# LPEDT_revA1_bikeit_MCU_RADIO.net
KiCad netlist of a schematic drawn in Altium Designer
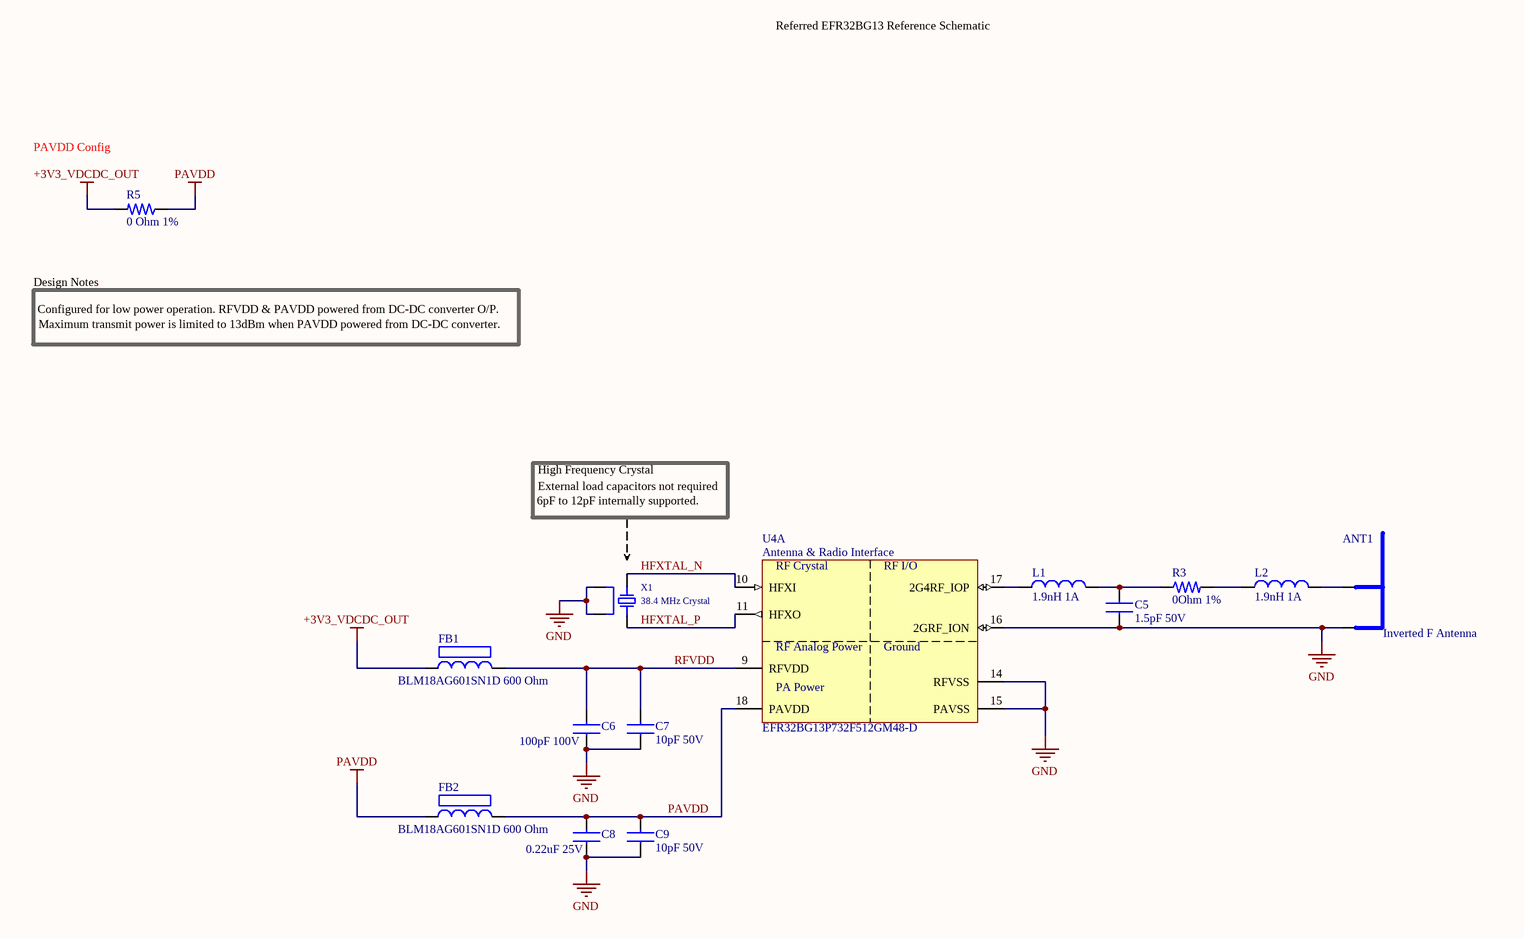
[diagram p0: LPEDT_revA1_bikeit_MCU_RADIO.SchDoc]

(export (version "E")
  (design (tool "Eeschema 10.0.6"))
  (components
    (comp (ref "ANT1")
      (value "Inverted F Antenna")
      (description "Inverted F antenna for BT")
      (libsource (lib "LPEDT_revA1_bikeit_IL") (part "Inverted F Antenna"))
    )
    (comp (ref "C5")
      (value "1.5pF 50V")
      (footprint "CAP_0403_1.00mm*0.50mm")
      (description "1.5pF ±0.1pF 50V Ceramic Capacitor C0G, NP0 0402 (1005 Metric)")
      (fields
        (field (name "MANUFACTURER") "Johanson Technology Inc.")
        (field (name "MANUFACTURER PART NUMBER") "500R07S1R5BV4T")
      )
      (libsource (lib "LPEDT_revA1_bikeit") (part "500R07S1R5BV4T"))
    )
    (comp (ref "C6")
      (value "100pF 100V")
      (footprint "CAP_0603_1.60mm*0.80mm")
      (description "Multilayer Ceramic Capacitors MLCC - SMD/SMT 100pF 100Volts C0G 0.01")
      (fields
        (field (name "MANUFACTURER") "Murata")
        (field (name "MANUFACTURER PART NUMBER") "GRM1885C2A101FA01D")
      )
      (libsource (lib "LPEDT_revA1_bikeit_IL") (part "GRM1885C2A101FA01D"))
    )
    (comp (ref "C7")
      (value "10pF 50V")
      (footprint "CAP_0603_1.60mm*0.80mm")
      (description "Cap Ceramic 10pF 50V C0G 1% SMD 0603 125C T/R")
      (fields
        (field (name "MANUFACTURER") "Murata")
        (field (name "MANUFACTURER PART NUMBER") "GRM1885C1H100FA01D")
      )
      (libsource (lib "LPEDT_revA1_bikeit_IL") (part "GRM1885C1H100FA01D"))
    )
    (comp (ref "C8")
      (value "0.22uF 25V")
      (footprint "CAP_0603_1.60mm*0.80mm")
      (description "Capacitor 220 nF 25 VDC PU=4000 ST, GRM188R71E224KA88D, Murata")
      (fields
        (field (name "MANUFACTURER") "Murata")
        (field (name "MANUFACTURER PART NUMBER") "GRM188R71E224KA88D")
      )
      (libsource (lib "LPEDT_revA1_bikeit_IL") (part "GRM188R71E224KA88D"))
    )
    (comp (ref "C9")
      (value "10pF 50V")
      (footprint "CAP_0603_1.60mm*0.80mm")
      (description "Cap Ceramic 10pF 50V C0G 1% SMD 0603 125C T/R")
      (fields
        (field (name "MANUFACTURER") "Murata")
        (field (name "MANUFACTURER PART NUMBER") "GRM1885C1H100FA01D")
      )
      (libsource (lib "LPEDT_revA1_bikeit_IL") (part "GRM1885C1H100FA01D"))
    )
    (comp (ref "FB1")
      (value "BLM18AG601SN1D 600 Ohm")
      (footprint "Chip2PinSM127P600-8N")
      (description "Ferrite Bead, 0603 / 1608, 600 ohm, 500 mA, Série BLM18A, 0.38 ohm, ± 25%")
      (fields
        (field (name "MANUFACTURER") "Murata")
        (field (name "MANUFACTURER PART NUMBER") "BLM18AG601SN1D")
      )
      (libsource (lib "LPEDT_revA1_bikeit_IL") (part "BLM18AG601SN1D"))
    )
    (comp (ref "FB2")
      (value "BLM18AG601SN1D 600 Ohm")
      (footprint "Chip2PinSM127P600-8N")
      (description "Ferrite Bead, 0603 / 1608, 600 ohm, 500 mA, Série BLM18A, 0.38 ohm, ± 25%")
      (fields
        (field (name "MANUFACTURER") "Murata")
        (field (name "MANUFACTURER PART NUMBER") "BLM18AG601SN1D")
      )
      (libsource (lib "LPEDT_revA1_bikeit_IL") (part "BLM18AG601SN1D"))
    )
    (comp (ref "L1")
      (value "1.9nH 1A")
      (description "1.9nH Unshielded Multilayer Inductor 1A 50mOhm Max 0402 (1005 Metric)")
      (libsource (lib "LPEDT_revA1_bikeit_IL") (part "LQG15WZ1N9S02D"))
    )
    (comp (ref "L2")
      (value "1.9nH 1A")
      (description "1.9nH Unshielded Multilayer Inductor 1A 50mOhm Max 0402 (1005 Metric)")
      (libsource (lib "LPEDT_revA1_bikeit_IL") (part "LQG15WZ1N9S02D"))
    )
    (comp (ref "R3")
      (value "0Ohm 1%")
      (footprint "RESC1005X04N")
      (description "RES 0 OHM JUMPER 1/16W 0402")
      (fields
        (field (name "MANUFACTURER") "Stackpole Electronics")
        (field (name "MANUFACTURER PART NUMBER") "RMCF0402ZT0R00")
      )
      (libsource (lib "LPEDT_revA1_bikeit_IL") (part "RMCF0402ZT0R00"))
    )
    (comp (ref "R5")
      (value "0 Ohm 1%")
      (footprint "RESC1005X04N")
      (description "RES 0 OHM JUMPER 1/16W 0402")
      (fields
        (field (name "MANUFACTURER") "Stackpole Electronics")
        (field (name "MANUFACTURER PART NUMBER") "RMCF0402ZT0R00")
      )
      (libsource (lib "LPEDT_revA1_bikeit_IL") (part "RMCF0402ZT0R00"))
    )
    (comp (ref "U4")
      (value "EFR32BG13P732F512GM48-D")
      (footprint "QFN50P700X700X90_HS-49N")
      (description "BLUE GECKO QFN48 2.4 GHZ 512KB 6")
      (fields (field (name "MANUFACTURER") "Silicon Labs"))
      (libsource (lib "LPEDT_revA1_bikeit") (part "EFR32BG13P732F512GM48-D"))
    )
    (comp (ref "X1")
      (value "38.4 MHz Crystal")
      (description "CRYSTAL 38.4000MHZ 8PF SMD")
      (fields
        (field (name "MANUFACTURER") "Kyocera AVX")
        (field (name "MANUFACTURER PART NUMBER") "CX2016DB38400D0FLJCC")
      )
      (libsource (lib "LPEDT_revA1_bikeit") (part "CX2016DB38400D0FLJCC"))
    )
  )
  (nets
    (net (code "1") (name "+3V3_VDCDC_OUT") (class "Default")
      (node (ref "FB1") (pin "1") (pinfunction "1_1") (pintype "passive"))
      (node (ref "R5") (pin "2") (pinfunction "2_2") (pintype "passive"))
    )
    (net (code "2") (name "/HFXTAL_N") (class "Default")
      (node (ref "U4") (pin "10") (pinfunction "HFXI_10") (pintype "input"))
      (node (ref "X1") (pin "3") (pinfunction "HOT_3") (pintype "passive"))
    )
    (net (code "3") (name "/HFXTAL_P") (class "Default")
      (node (ref "U4") (pin "11") (pinfunction "HFXO_11") (pintype "output"))
      (node (ref "X1") (pin "1") (pinfunction "HOT_1") (pintype "passive"))
    )
    (net (code "4") (name "/RFVDD") (class "Default")
      (node (ref "C6") (pin "1") (pinfunction "1_1") (pintype "passive"))
      (node (ref "C7") (pin "1") (pinfunction "1_1") (pintype "passive"))
      (node (ref "FB1") (pin "2") (pinfunction "2_2") (pintype "passive"))
      (node (ref "U4") (pin "9") (pinfunction "RFVDD_9") (pintype "power_in"))
    )
    (net (code "5") (name "GND") (class "Default")
      (node (ref "ANT1") (pin "2") (pinfunction "GND_2") (pintype "power_in"))
      (node (ref "C5") (pin "2") (pinfunction "2_2") (pintype "passive"))
      (node (ref "C6") (pin "2") (pinfunction "2_2") (pintype "passive"))
      (node (ref "C7") (pin "2") (pinfunction "2_2") (pintype "passive"))
      (node (ref "C8") (pin "2") (pinfunction "2_2") (pintype "passive"))
      (node (ref "C9") (pin "2") (pinfunction "2_2") (pintype "passive"))
      (node (ref "U4") (pin "14") (pinfunction "RFVSS_14") (pintype "power_in"))
      (node (ref "U4") (pin "15") (pinfunction "PAVSS_15") (pintype "power_in"))
      (node (ref "U4") (pin "16") (pinfunction "2GRF_ION_16") (pintype "bidirectional"))
      (node (ref "X1") (pin "2") (pinfunction "GND_2") (pintype "passive"))
      (node (ref "X1") (pin "4") (pinfunction "GND_4") (pintype "passive"))
    )
    (net (code "6") (name "Net-(ANT1-FEED)") (class "Default")
      (node (ref "ANT1") (pin "1") (pinfunction "FEED_1") (pintype "passive"))
      (node (ref "L2") (pin "2") (pinfunction "2_2") (pintype "passive"))
    )
    (net (code "7") (name "Net-(C5-Pad1)") (class "Default")
      (node (ref "C5") (pin "1") (pinfunction "1_1") (pintype "passive"))
      (node (ref "L1") (pin "2") (pinfunction "2_2") (pintype "passive"))
      (node (ref "R3") (pin "1") (pinfunction "1_1") (pintype "passive"))
    )
    (net (code "8") (name "Net-(L2-Pad1)") (class "Default")
      (node (ref "L2") (pin "1") (pinfunction "1_1") (pintype "passive"))
      (node (ref "R3") (pin "2") (pinfunction "2_2") (pintype "passive"))
    )
    (net (code "9") (name "Net-(U4A-2G4RF_IOP)") (class "Default")
      (node (ref "L1") (pin "1") (pinfunction "1_1") (pintype "passive"))
      (node (ref "U4") (pin "17") (pinfunction "2G4RF_IOP_17") (pintype "bidirectional"))
    )
    (net (code "10") (name "PAVDD") (class "Default")
      (node (ref "C8") (pin "1") (pinfunction "1_1") (pintype "passive"))
      (node (ref "C9") (pin "1") (pinfunction "1_1") (pintype "passive"))
      (node (ref "FB2") (pin "1") (pinfunction "1_1") (pintype "passive"))
      (node (ref "FB2") (pin "2") (pinfunction "2_2") (pintype "passive"))
      (node (ref "R5") (pin "1") (pinfunction "1_1") (pintype "passive"))
      (node (ref "U4") (pin "18") (pinfunction "PAVDD_18") (pintype "power_in"))
    )
  )
)
